# ibmpc.net
KiCad netlist of a schematic drawn in EAGLE
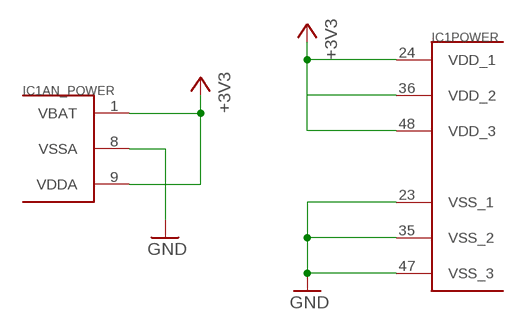
[diagram p0: schematic, sheet 1, part 1 of 2]
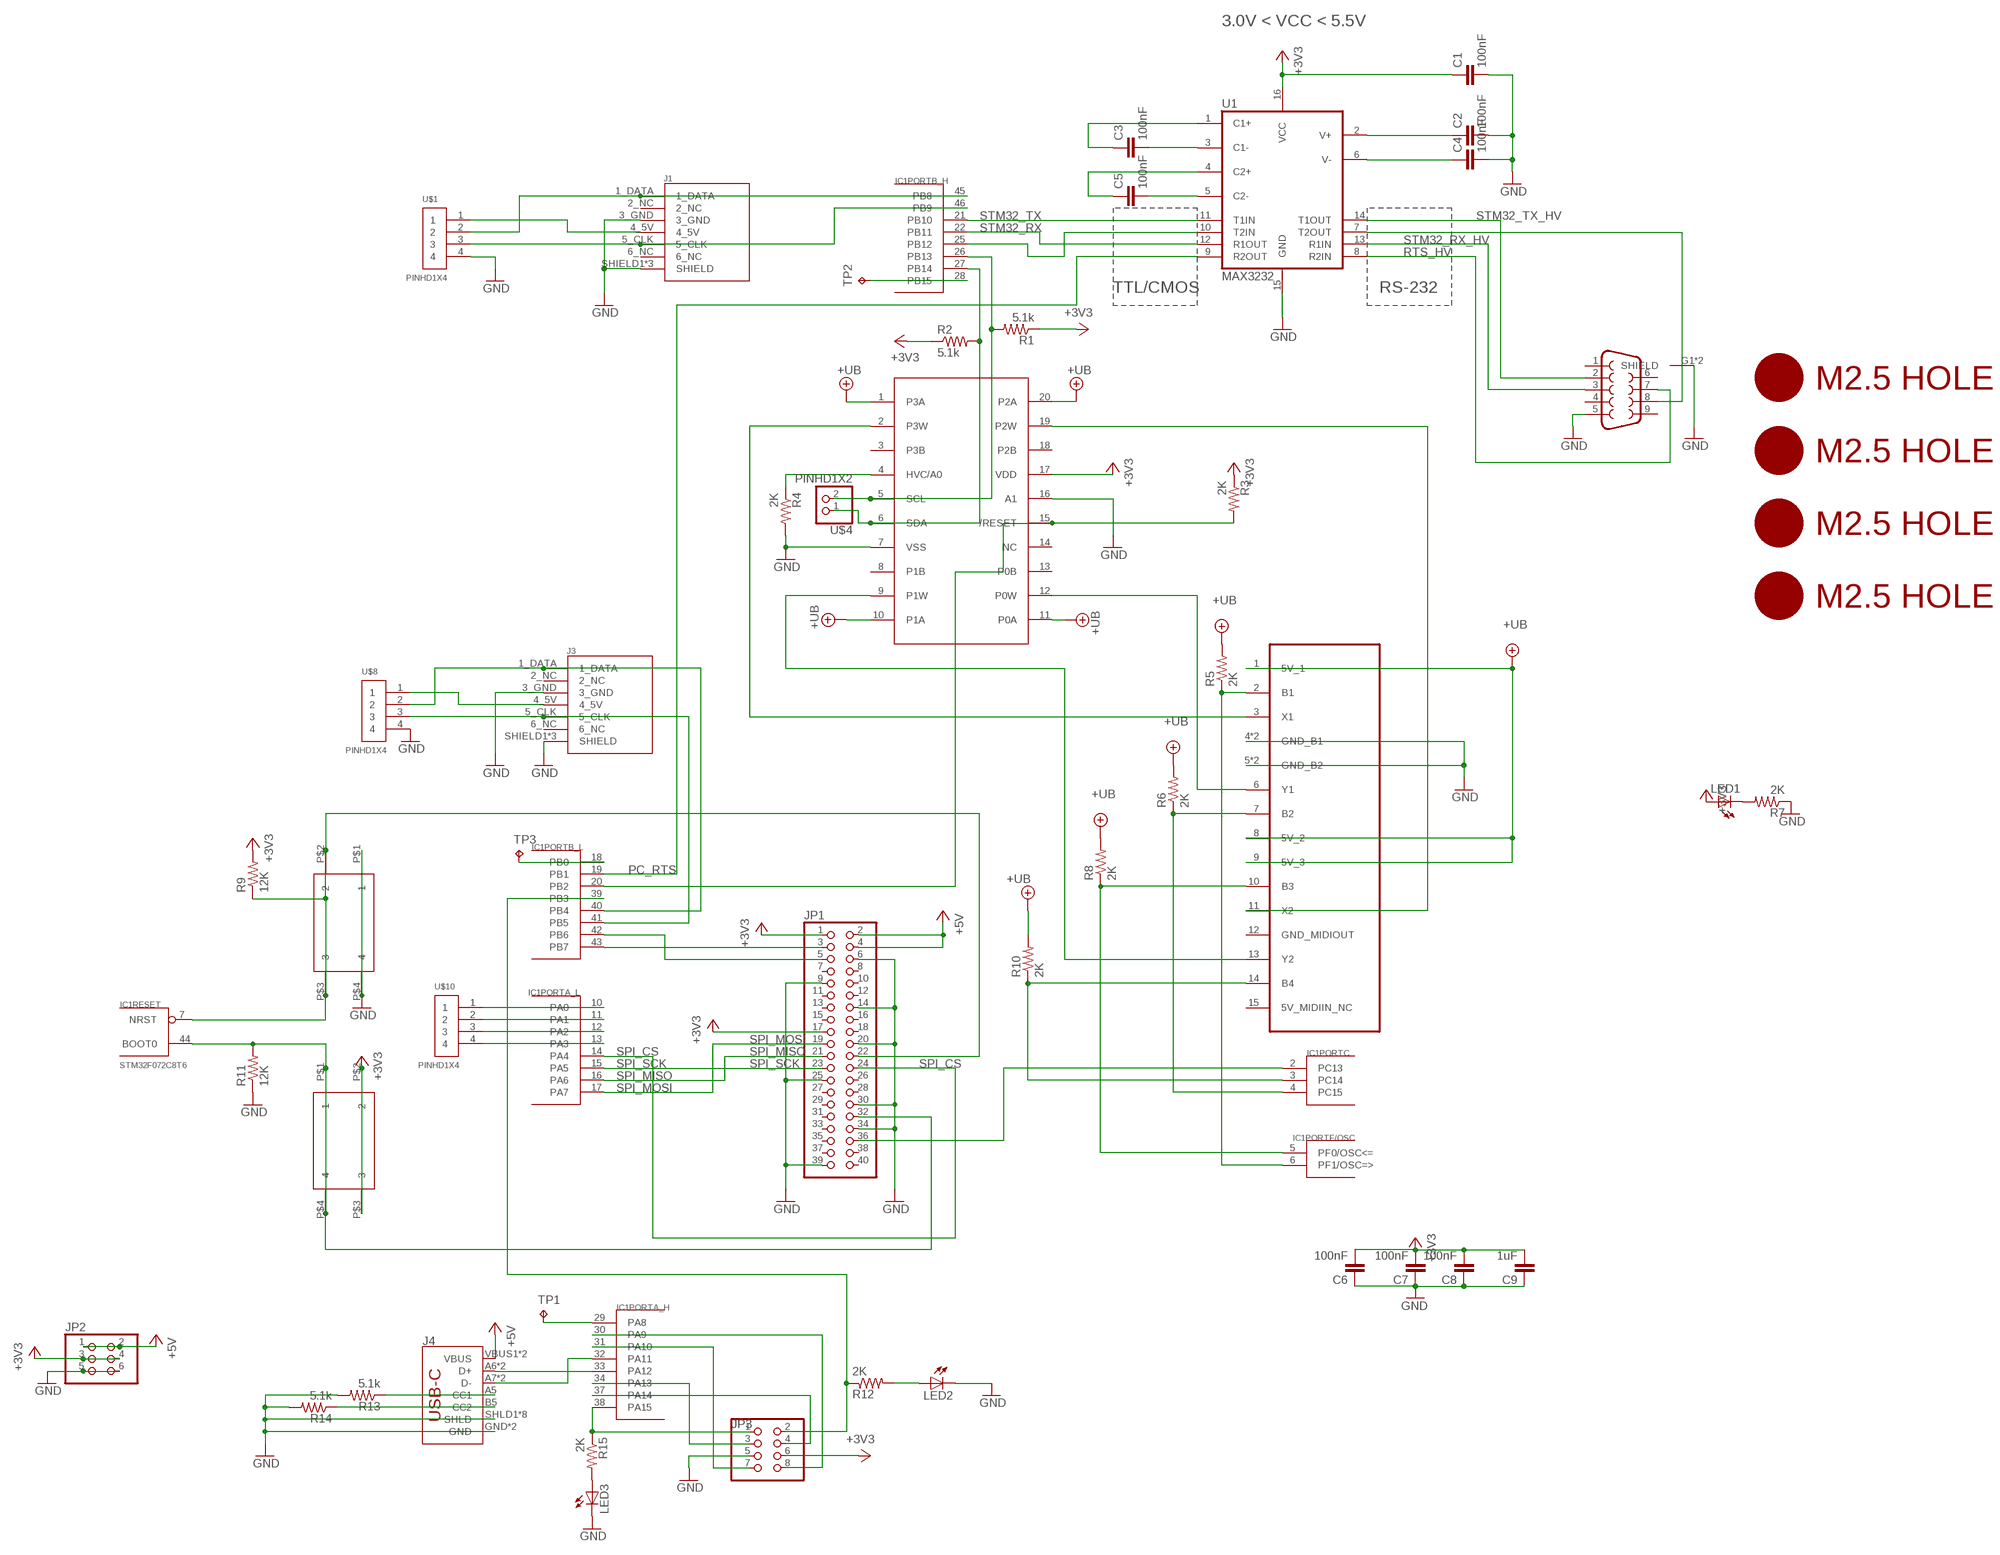
[diagram p1: schematic, sheet 1, part 2 of 2]

(export (version "E")
  (design (tool "Eeschema 10.0.6"))
  (components
    (comp (ref "C1")
      (value "100nF")
      (footprint "eagle-import:0805@1")
      (libsource (lib "eagle-import") (part "CAP0805"))
    )
    (comp (ref "C2")
      (value "100nF")
      (footprint "eagle-import:0805@1")
      (libsource (lib "eagle-import") (part "CAP0805"))
    )
    (comp (ref "C3")
      (value "100nF")
      (footprint "eagle-import:0805@1")
      (libsource (lib "eagle-import") (part "CAP0805"))
    )
    (comp (ref "C4")
      (value "100nF")
      (footprint "eagle-import:0805@1")
      (libsource (lib "eagle-import") (part "CAP0805"))
    )
    (comp (ref "C5")
      (value "100nF")
      (footprint "eagle-import:0805@1")
      (libsource (lib "eagle-import") (part "CAP0805"))
    )
    (comp (ref "C6")
      (value "100nF")
      (footprint "eagle-import:0805@1")
      (libsource (lib "eagle-import") (part "CAP0805"))
    )
    (comp (ref "C7")
      (value "100nF")
      (footprint "eagle-import:0805@1")
      (libsource (lib "eagle-import") (part "CAP0805"))
    )
    (comp (ref "C8")
      (value "100nF")
      (footprint "eagle-import:0805@1")
      (libsource (lib "eagle-import") (part "CAP0805"))
    )
    (comp (ref "C9")
      (value "1uF")
      (footprint "eagle-import:0805@1")
      (libsource (lib "eagle-import") (part "CAP0805"))
    )
    (comp (ref "IC1")
      (value "STM32F072C8T6")
      (footprint "eagle-import:TQFP48")
      (libsource (lib "eagle-import") (part "STM32F072C8T6"))
    )
    (comp (ref "J1")
      (value "DIN7")
      (footprint "eagle-import:DIN7")
      (libsource (lib "eagle-import") (part "DIN7"))
    )
    (comp (ref "J2")
      (value "DB9MALE")
      (footprint "eagle-import:DB9_MALE")
      (libsource (lib "eagle-import") (part "DB9MALE"))
    )
    (comp (ref "J3")
      (value "DIN7")
      (footprint "eagle-import:DIN7")
      (libsource (lib "eagle-import") (part "DIN7"))
    )
    (comp (ref "J4")
      (value "USB_C16PIN")
      (footprint "eagle-import:USB-C-16P")
      (libsource (lib "eagle-import") (part "USB_C16PIN"))
    )
    (comp (ref "JP1")
      (value "PINHD-2X20-BIG")
      (footprint "eagle-import:2X20-BIG")
      (libsource (lib "eagle-import") (part "PINHD-2X20-BIG"))
    )
    (comp (ref "JP2")
      (value "PINHD-2X3")
      (footprint "eagle-import:2X03")
      (libsource (lib "eagle-import") (part "PINHD-2X3"))
    )
    (comp (ref "JP3")
      (value "PINHD-2X4")
      (footprint "eagle-import:2X04")
      (libsource (lib "eagle-import") (part "PINHD-2X4"))
    )
    (comp (ref "LED1")
      (value "LEDCHIP-LED0805")
      (footprint "eagle-import:CHIP-LED0805")
      (libsource (lib "eagle-import") (part "LEDCHIP-LED0805"))
    )
    (comp (ref "LED2")
      (value "LEDCHIP-LED0805")
      (footprint "eagle-import:CHIP-LED0805")
      (libsource (lib "eagle-import") (part "LEDCHIP-LED0805"))
    )
    (comp (ref "LED3")
      (value "LEDCHIP-LED0805")
      (footprint "eagle-import:CHIP-LED0805")
      (libsource (lib "eagle-import") (part "LEDCHIP-LED0805"))
    )
    (comp (ref "R1")
      (value "5.1k")
      (footprint "eagle-import:0805")
      (libsource (lib "eagle-import") (part "RESISTOR0805-RES"))
    )
    (comp (ref "R2")
      (value "5.1k")
      (footprint "eagle-import:0805")
      (libsource (lib "eagle-import") (part "RESISTOR0805-RES"))
    )
    (comp (ref "R3")
      (value "2K")
      (footprint "eagle-import:0805")
      (libsource (lib "eagle-import") (part "RESISTOR0805-RES"))
    )
    (comp (ref "R4")
      (value "2K")
      (footprint "eagle-import:0805")
      (libsource (lib "eagle-import") (part "RESISTOR0805-RES"))
    )
    (comp (ref "R5")
      (value "2K")
      (footprint "eagle-import:0805")
      (libsource (lib "eagle-import") (part "RESISTOR0805-RES"))
    )
    (comp (ref "R6")
      (value "2K")
      (footprint "eagle-import:0805")
      (libsource (lib "eagle-import") (part "RESISTOR0805-RES"))
    )
    (comp (ref "R7")
      (value "2K")
      (footprint "eagle-import:0805")
      (libsource (lib "eagle-import") (part "RESISTOR0805-RES"))
    )
    (comp (ref "R8")
      (value "2K")
      (footprint "eagle-import:0805")
      (libsource (lib "eagle-import") (part "RESISTOR0805-RES"))
    )
    (comp (ref "R9")
      (value "12K")
      (footprint "eagle-import:0805")
      (libsource (lib "eagle-import") (part "RESISTOR0805-RES"))
    )
    (comp (ref "R10")
      (value "2K")
      (footprint "eagle-import:0805")
      (libsource (lib "eagle-import") (part "RESISTOR0805-RES"))
    )
    (comp (ref "R11")
      (value "12K")
      (footprint "eagle-import:0805")
      (libsource (lib "eagle-import") (part "RESISTOR0805-RES"))
    )
    (comp (ref "R12")
      (value "2K")
      (footprint "eagle-import:0805")
      (libsource (lib "eagle-import") (part "RESISTOR0805-RES"))
    )
    (comp (ref "R13")
      (value "5.1k")
      (footprint "eagle-import:0805")
      (libsource (lib "eagle-import") (part "RESISTOR0805-RES"))
    )
    (comp (ref "R14")
      (value "5.1k")
      (footprint "eagle-import:0805")
      (libsource (lib "eagle-import") (part "RESISTOR0805-RES"))
    )
    (comp (ref "R15")
      (value "2K")
      (footprint "eagle-import:0805")
      (libsource (lib "eagle-import") (part "RESISTOR0805-RES"))
    )
    (comp (ref "SW1")
      (value "324_SW")
      (footprint "eagle-import:342_SWICH_FOOT")
      (libsource (lib "eagle-import") (part "324_SW"))
    )
    (comp (ref "SW2")
      (value "324_SW")
      (footprint "eagle-import:342_SWICH_FOOT")
      (libsource (lib "eagle-import") (part "324_SW"))
    )
    (comp (ref "TP1")
      (value "TPTP12R")
      (footprint "eagle-import:TP12R")
      (libsource (lib "eagle-import") (part "TPTP12R"))
    )
    (comp (ref "TP2")
      (value "TPTP12R")
      (footprint "eagle-import:TP12R")
      (libsource (lib "eagle-import") (part "TPTP12R"))
    )
    (comp (ref "TP3")
      (value "TPTP12R")
      (footprint "eagle-import:TP12R")
      (libsource (lib "eagle-import") (part "TPTP12R"))
    )
    (comp (ref "U$1")
      (value "PINHD1X4")
      (footprint "eagle-import:1X04-CLEANBIG")
      (libsource (lib "eagle-import") (part "PINHD1X4"))
    )
    (comp (ref "U$2")
      (value "M2.5HOLE")
      (footprint "eagle-import:M2.5HOLE")
      (libsource (lib "eagle-import") (part "M2.5HOLE"))
    )
    (comp (ref "U$3")
      (value "M2.5HOLE")
      (footprint "eagle-import:M2.5HOLE")
      (libsource (lib "eagle-import") (part "M2.5HOLE"))
    )
    (comp (ref "U$4")
      (value "PINHD1X2")
      (footprint "eagle-import:1X02")
      (libsource (lib "eagle-import") (part "PINHD1X2"))
    )
    (comp (ref "U$5")
      (value "MCP4451")
      (footprint "eagle-import:TSSOP20")
      (libsource (lib "eagle-import") (part "MCP4451"))
    )
    (comp (ref "U$6")
      (value "M2.5HOLE")
      (footprint "eagle-import:M2.5HOLE")
      (libsource (lib "eagle-import") (part "M2.5HOLE"))
    )
    (comp (ref "U$7")
      (value "M2.5HOLE")
      (footprint "eagle-import:M2.5HOLE")
      (libsource (lib "eagle-import") (part "M2.5HOLE"))
    )
    (comp (ref "U$8")
      (value "PINHD1X4")
      (footprint "eagle-import:1X04-CLEANBIG")
      (libsource (lib "eagle-import") (part "PINHD1X4"))
    )
    (comp (ref "U$9")
      (value "GAMEPORT_15P")
      (footprint "eagle-import:DA15")
      (libsource (lib "eagle-import") (part "GAMEPORT_15P"))
    )
    (comp (ref "U$10")
      (value "PINHD1X4")
      (footprint "eagle-import:1X04-CLEANBIG")
      (libsource (lib "eagle-import") (part "PINHD1X4"))
    )
    (comp (ref "U1")
      (value "MAX3232")
      (footprint "eagle-import:SO016")
      (libsource (lib "eagle-import") (part "MAX232SOIC16"))
    )
  )
  (nets
    (net (code "1") (name "+3V3") (class "Default")
      (node (ref "C1") (pin "1") (pinfunction "1_1") (pintype "passive"))
      (node (ref "C6") (pin "2") (pinfunction "2_2") (pintype "passive"))
      (node (ref "C7") (pin "2") (pinfunction "2_2") (pintype "passive"))
      (node (ref "C8") (pin "2") (pinfunction "2_2") (pintype "passive"))
      (node (ref "C9") (pin "2") (pinfunction "2_2") (pintype "passive"))
      (node (ref "IC1") (pin "1") (pinfunction "VBAT_1") (pintype "power_in"))
      (node (ref "IC1") (pin "24") (pinfunction "VDD_1_24") (pintype "power_in"))
      (node (ref "IC1") (pin "36") (pinfunction "VDD_2_36") (pintype "power_in"))
      (node (ref "IC1") (pin "48") (pinfunction "VDD_3_48") (pintype "power_in"))
      (node (ref "IC1") (pin "9") (pinfunction "VDDA_9") (pintype "power_in"))
      (node (ref "JP1") (pin "1") (pinfunction "1_1") (pintype "passive"))
      (node (ref "JP1") (pin "17") (pinfunction "17_17") (pintype "passive"))
      (node (ref "JP2") (pin "3") (pinfunction "3_3") (pintype "passive"))
      (node (ref "JP2") (pin "4") (pinfunction "4_4") (pintype "passive"))
      (node (ref "JP3") (pin "6") (pinfunction "6_6") (pintype "passive"))
      (node (ref "LED1") (pin "A") (pinfunction "A_A") (pintype "passive"))
      (node (ref "R1") (pin "1") (pinfunction "1_1") (pintype "passive"))
      (node (ref "R2") (pin "1") (pinfunction "1_1") (pintype "passive"))
      (node (ref "R3") (pin "1") (pinfunction "1_1") (pintype "passive"))
      (node (ref "R9") (pin "2") (pinfunction "2_2") (pintype "passive"))
      (node (ref "SW2") (pin "P$2") (pinfunction "2_P$2") (pintype "bidirectional"))
      (node (ref "SW2") (pin "P$3") (pinfunction "3_P$3") (pintype "bidirectional"))
      (node (ref "U$5") (pin "17") (pinfunction "VDD_17") (pintype "bidirectional"))
      (node (ref "U1") (pin "16") (pinfunction "VCC_16") (pintype "bidirectional"))
    )
    (net (code "2") (name "+5V") (class "Default")
      (node (ref "J4") (pin "VBUS1") (pinfunction "VBUS_VBUS1") (pintype "bidirectional"))
      (node (ref "J4") (pin "VBUS2") (pinfunction "VBUS_VBUS2") (pintype "bidirectional"))
      (node (ref "JP1") (pin "2") (pinfunction "2_2") (pintype "passive"))
      (node (ref "JP1") (pin "4") (pinfunction "4_4") (pintype "passive"))
      (node (ref "JP2") (pin "1") (pinfunction "1_1") (pintype "passive"))
      (node (ref "JP2") (pin "2") (pinfunction "2_2") (pintype "passive"))
    )
    (net (code "3") (name "+UB") (class "Default")
      (node (ref "R10") (pin "2") (pinfunction "2_2") (pintype "passive"))
      (node (ref "R5") (pin "2") (pinfunction "2_2") (pintype "passive"))
      (node (ref "R6") (pin "2") (pinfunction "2_2") (pintype "passive"))
      (node (ref "R8") (pin "2") (pinfunction "2_2") (pintype "passive"))
      (node (ref "U$5") (pin "1") (pinfunction "P3A_1") (pintype "bidirectional"))
      (node (ref "U$5") (pin "10") (pinfunction "P1A_10") (pintype "bidirectional"))
      (node (ref "U$5") (pin "11") (pinfunction "P0A_11") (pintype "bidirectional"))
      (node (ref "U$5") (pin "20") (pinfunction "P2A_20") (pintype "bidirectional"))
      (node (ref "U$9") (pin "1") (pinfunction "5V_1_1") (pintype "bidirectional"))
      (node (ref "U$9") (pin "8") (pinfunction "5V_2_8") (pintype "bidirectional"))
      (node (ref "U$9") (pin "9") (pinfunction "5V_3_9") (pintype "bidirectional"))
    )
    (net (code "4") (name "/PC_RTS") (class "Default")
      (node (ref "IC1") (pin "19") (pinfunction "PB1_19") (pintype "bidirectional"))
      (node (ref "U1") (pin "9") (pinfunction "R2OUT_9") (pintype "output"))
    )
    (net (code "5") (name "/RTS_HV") (class "Default")
      (node (ref "J2") (pin "7") (pinfunction "7_7") (pintype "passive"))
      (node (ref "U1") (pin "8") (pinfunction "R2IN_8") (pintype "input"))
    )
    (net (code "6") (name "/SPI_CS") (class "Default")
      (node (ref "IC1") (pin "14") (pinfunction "PA4_14") (pintype "bidirectional"))
      (node (ref "JP1") (pin "24") (pinfunction "24_24") (pintype "passive"))
    )
    (net (code "7") (name "/SPI_MISO") (class "Default")
      (node (ref "IC1") (pin "16") (pinfunction "PA6_16") (pintype "bidirectional"))
      (node (ref "JP1") (pin "21") (pinfunction "21_21") (pintype "passive"))
    )
    (net (code "8") (name "/SPI_MOSI") (class "Default")
      (node (ref "IC1") (pin "17") (pinfunction "PA7_17") (pintype "bidirectional"))
      (node (ref "JP1") (pin "19") (pinfunction "19_19") (pintype "passive"))
    )
    (net (code "9") (name "/SPI_SCK") (class "Default")
      (node (ref "IC1") (pin "15") (pinfunction "PA5_15") (pintype "bidirectional"))
      (node (ref "JP1") (pin "23") (pinfunction "23_23") (pintype "passive"))
    )
    (net (code "10") (name "/STM32_RX") (class "Default")
      (node (ref "IC1") (pin "22") (pinfunction "PB11_22") (pintype "bidirectional"))
      (node (ref "U1") (pin "12") (pinfunction "R1OUT_12") (pintype "output"))
    )
    (net (code "11") (name "/STM32_RX_HV") (class "Default")
      (node (ref "J2") (pin "3") (pinfunction "3_3") (pintype "passive"))
      (node (ref "U1") (pin "13") (pinfunction "R1IN_13") (pintype "input"))
    )
    (net (code "12") (name "/STM32_TX") (class "Default")
      (node (ref "IC1") (pin "21") (pinfunction "PB10_21") (pintype "bidirectional"))
      (node (ref "U1") (pin "11") (pinfunction "T1IN_11") (pintype "input"))
    )
    (net (code "13") (name "/STM32_TX_HV") (class "Default")
      (node (ref "J2") (pin "2") (pinfunction "2_2") (pintype "passive"))
      (node (ref "U1") (pin "14") (pinfunction "T1OUT_14") (pintype "output"))
    )
    (net (code "14") (name "GND") (class "Default")
      (node (ref "C1") (pin "2") (pinfunction "2_2") (pintype "passive"))
      (node (ref "C2") (pin "2") (pinfunction "2_2") (pintype "passive"))
      (node (ref "C4") (pin "2") (pinfunction "2_2") (pintype "passive"))
      (node (ref "C6") (pin "1") (pinfunction "1_1") (pintype "passive"))
      (node (ref "C7") (pin "1") (pinfunction "1_1") (pintype "passive"))
      (node (ref "C8") (pin "1") (pinfunction "1_1") (pintype "passive"))
      (node (ref "C9") (pin "1") (pinfunction "1_1") (pintype "passive"))
      (node (ref "IC1") (pin "23") (pinfunction "VSS_1_23") (pintype "power_in"))
      (node (ref "IC1") (pin "35") (pinfunction "VSS_2_35") (pintype "power_in"))
      (node (ref "IC1") (pin "47") (pinfunction "VSS_3_47") (pintype "power_in"))
      (node (ref "IC1") (pin "8") (pinfunction "VSSA_8") (pintype "power_in"))
      (node (ref "J1") (pin "3_GND") (pinfunction "3_GND_3_GND") (pintype "bidirectional"))
      (node (ref "J1") (pin "SHIELD1") (pinfunction "SHIELD_SHIELD1") (pintype "bidirectional"))
      (node (ref "J1") (pin "SHIELD2") (pinfunction "SHIELD_SHIELD2") (pintype "bidirectional"))
      (node (ref "J1") (pin "SHIELD3") (pinfunction "SHIELD_SHIELD3") (pintype "bidirectional"))
      (node (ref "J2") (pin "5") (pinfunction "5_5") (pintype "passive"))
      (node (ref "J2") (pin "G1") (pinfunction "SHIELD_G1") (pintype "bidirectional"))
      (node (ref "J2") (pin "G2") (pinfunction "SHIELD_G2") (pintype "bidirectional"))
      (node (ref "J3") (pin "3_GND") (pinfunction "3_GND_3_GND") (pintype "bidirectional"))
      (node (ref "J3") (pin "SHIELD1") (pinfunction "SHIELD_SHIELD1") (pintype "bidirectional"))
      (node (ref "J3") (pin "SHIELD2") (pinfunction "SHIELD_SHIELD2") (pintype "bidirectional"))
      (node (ref "J3") (pin "SHIELD3") (pinfunction "SHIELD_SHIELD3") (pintype "bidirectional"))
      (node (ref "J4") (pin "GND") (pinfunction "GND_GND") (pintype "bidirectional"))
      (node (ref "J4") (pin "GND2") (pinfunction "GND_GND2") (pintype "bidirectional"))
      (node (ref "J4") (pin "SHLD1") (pinfunction "SHLD_SHLD1") (pintype "bidirectional"))
      (node (ref "J4") (pin "SHLD2") (pinfunction "SHLD_SHLD2") (pintype "bidirectional"))
      (node (ref "J4") (pin "SHLD3") (pinfunction "SHLD_SHLD3") (pintype "bidirectional"))
      (node (ref "J4") (pin "SHLD4") (pinfunction "SHLD_SHLD4") (pintype "bidirectional"))
      (node (ref "J4") (pin "SHLD5") (pinfunction "SHLD_SHLD5") (pintype "bidirectional"))
      (node (ref "J4") (pin "SHLD6") (pinfunction "SHLD_SHLD6") (pintype "bidirectional"))
      (node (ref "J4") (pin "SHLD7") (pinfunction "SHLD_SHLD7") (pintype "bidirectional"))
      (node (ref "J4") (pin "SHLD8") (pinfunction "SHLD_SHLD8") (pintype "bidirectional"))
      (node (ref "JP1") (pin "14") (pinfunction "14_14") (pintype "passive"))
      (node (ref "JP1") (pin "20") (pinfunction "20_20") (pintype "passive"))
      (node (ref "JP1") (pin "25") (pinfunction "25_25") (pintype "passive"))
      (node (ref "JP1") (pin "30") (pinfunction "30_30") (pintype "passive"))
      (node (ref "JP1") (pin "34") (pinfunction "34_34") (pintype "passive"))
      (node (ref "JP1") (pin "39") (pinfunction "39_39") (pintype "passive"))
      (node (ref "JP1") (pin "6") (pinfunction "6_6") (pintype "passive"))
      (node (ref "JP1") (pin "9") (pinfunction "9_9") (pintype "passive"))
      (node (ref "JP2") (pin "5") (pinfunction "5_5") (pintype "passive"))
      (node (ref "JP2") (pin "6") (pinfunction "6_6") (pintype "passive"))
      (node (ref "JP3") (pin "5") (pinfunction "5_5") (pintype "passive"))
      (node (ref "LED2") (pin "C") (pinfunction "C_C") (pintype "passive"))
      (node (ref "LED3") (pin "C") (pinfunction "C_C") (pintype "passive"))
      (node (ref "R11") (pin "1") (pinfunction "1_1") (pintype "passive"))
      (node (ref "R13") (pin "2") (pinfunction "2_2") (pintype "passive"))
      (node (ref "R14") (pin "2") (pinfunction "2_2") (pintype "passive"))
      (node (ref "R4") (pin "2") (pinfunction "2_2") (pintype "passive"))
      (node (ref "R7") (pin "1") (pinfunction "1_1") (pintype "passive"))
      (node (ref "SW1") (pin "P$1") (pinfunction "1_P$1") (pintype "bidirectional"))
      (node (ref "SW1") (pin "P$4") (pinfunction "4_P$4") (pintype "bidirectional"))
      (node (ref "U$1") (pin "4") (pinfunction "4_4") (pintype "bidirectional"))
      (node (ref "U$5") (pin "16") (pinfunction "A1_16") (pintype "bidirectional"))
      (node (ref "U$5") (pin "7") (pinfunction "VSS_7") (pintype "bidirectional"))
      (node (ref "U$8") (pin "4") (pinfunction "4_4") (pintype "bidirectional"))
      (node (ref "U$9") (pin "4") (pinfunction "GND_B1_4") (pintype "bidirectional"))
      (node (ref "U$9") (pin "5") (pinfunction "GND_B2_5") (pintype "bidirectional"))
      (node (ref "U$9") (pin "G1") (pinfunction "GND_B1_G1") (pintype "bidirectional"))
      (node (ref "U$9") (pin "G2") (pinfunction "GND_B2_G2") (pintype "bidirectional"))
      (node (ref "U1") (pin "15") (pinfunction "GND_15") (pintype "bidirectional"))
    )
    (net (code "15") (name "Net-(IC1B-PA8)") (class "Default")
      (node (ref "IC1") (pin "29") (pinfunction "PA8_29") (pintype "bidirectional"))
      (node (ref "TP1") (pin "TP") (pinfunction "TP_TP") (pintype "input"))
    )
    (net (code "16") (name "Net-(IC1B-PA9)") (class "Default")
      (node (ref "IC1") (pin "30") (pinfunction "PA9_30") (pintype "bidirectional"))
      (node (ref "JP3") (pin "8") (pinfunction "8_8") (pintype "passive"))
    )
    (net (code "17") (name "Net-(IC1B-PA10)") (class "Default")
      (node (ref "IC1") (pin "31") (pinfunction "PA10_31") (pintype "bidirectional"))
      (node (ref "JP3") (pin "7") (pinfunction "7_7") (pintype "passive"))
    )
    (net (code "18") (name "Net-(IC1B-PA11)") (class "Default")
      (node (ref "IC1") (pin "32") (pinfunction "PA11_32") (pintype "bidirectional"))
      (node (ref "J4") (pin "A7") (pinfunction "D-_A7") (pintype "bidirectional"))
      (node (ref "J4") (pin "B7") (pinfunction "D-_B7") (pintype "bidirectional"))
    )
    (net (code "19") (name "Net-(IC1B-PA12)") (class "Default")
      (node (ref "IC1") (pin "33") (pinfunction "PA12_33") (pintype "bidirectional"))
      (node (ref "J4") (pin "A6") (pinfunction "D+_A6") (pintype "bidirectional"))
      (node (ref "J4") (pin "B6") (pinfunction "D+_B6") (pintype "bidirectional"))
    )
    (net (code "20") (name "Net-(IC1B-PA13)") (class "Default")
      (node (ref "IC1") (pin "34") (pinfunction "PA13_34") (pintype "bidirectional"))
      (node (ref "JP3") (pin "3") (pinfunction "3_3") (pintype "passive"))
    )
    (net (code "21") (name "Net-(IC1B-PA14)") (class "Default")
      (node (ref "IC1") (pin "37") (pinfunction "PA14_37") (pintype "bidirectional"))
      (node (ref "JP3") (pin "4") (pinfunction "4_4") (pintype "passive"))
    )
    (net (code "22") (name "Net-(IC1B-PA15)") (class "Default")
      (node (ref "IC1") (pin "38") (pinfunction "PA15_38") (pintype "bidirectional"))
      (node (ref "JP3") (pin "1") (pinfunction "1_1") (pintype "passive"))
      (node (ref "R15") (pin "1") (pinfunction "1_1") (pintype "passive"))
    )
    (net (code "23") (name "Net-(IC1C-PA0)") (class "Default")
      (node (ref "IC1") (pin "10") (pinfunction "PA0_10") (pintype "bidirectional"))
      (node (ref "U$10") (pin "1") (pinfunction "1_1") (pintype "bidirectional"))
    )
    (net (code "24") (name "Net-(IC1C-PA1)") (class "Default")
      (node (ref "IC1") (pin "11") (pinfunction "PA1_11") (pintype "bidirectional"))
      (node (ref "U$10") (pin "2") (pinfunction "2_2") (pintype "bidirectional"))
    )
    (net (code "25") (name "Net-(IC1C-PA2)") (class "Default")
      (node (ref "IC1") (pin "12") (pinfunction "PA2_12") (pintype "bidirectional"))
      (node (ref "U$10") (pin "3") (pinfunction "3_3") (pintype "bidirectional"))
    )
    (net (code "26") (name "Net-(IC1C-PA3)") (class "Default")
      (node (ref "IC1") (pin "13") (pinfunction "PA3_13") (pintype "bidirectional"))
      (node (ref "U$10") (pin "4") (pinfunction "4_4") (pintype "bidirectional"))
    )
    (net (code "27") (name "Net-(IC1D-PB8)") (class "Default")
      (node (ref "IC1") (pin "45") (pinfunction "PB8_45") (pintype "bidirectional"))
      (node (ref "J1") (pin "1_DATA") (pinfunction "1_DATA_1_DATA") (pintype "bidirectional"))
      (node (ref "U$1") (pin "2") (pinfunction "2_2") (pintype "bidirectional"))
    )
    (net (code "28") (name "Net-(IC1D-PB9)") (class "Default")
      (node (ref "IC1") (pin "46") (pinfunction "PB9_46") (pintype "bidirectional"))
      (node (ref "J1") (pin "5_CLK") (pinfunction "5_CLK_5_CLK") (pintype "bidirectional"))
      (node (ref "U$1") (pin "3") (pinfunction "3_3") (pintype "bidirectional"))
    )
    (net (code "29") (name "Net-(IC1D-PB12)") (class "Default")
      (node (ref "IC1") (pin "25") (pinfunction "PB12_25") (pintype "bidirectional"))
      (node (ref "U1") (pin "10") (pinfunction "T2IN_10") (pintype "input"))
    )
    (net (code "30") (name "Net-(IC1D-PB13)") (class "Default")
      (node (ref "IC1") (pin "26") (pinfunction "PB13_26") (pintype "bidirectional"))
      (node (ref "R1") (pin "2") (pinfunction "2_2") (pintype "passive"))
      (node (ref "U$4") (pin "2") (pinfunction "2_2") (pintype "passive"))
      (node (ref "U$5") (pin "5") (pinfunction "SCL_5") (pintype "bidirectional"))
    )
    (net (code "31") (name "Net-(IC1D-PB14)") (class "Default")
      (node (ref "IC1") (pin "27") (pinfunction "PB14_27") (pintype "bidirectional"))
      (node (ref "R2") (pin "2") (pinfunction "2_2") (pintype "passive"))
      (node (ref "U$4") (pin "1") (pinfunction "1_1") (pintype "passive"))
      (node (ref "U$5") (pin "6") (pinfunction "SDA_6") (pintype "bidirectional"))
    )
    (net (code "32") (name "Net-(IC1D-PB15)") (class "Default")
      (node (ref "IC1") (pin "28") (pinfunction "PB15_28") (pintype "bidirectional"))
      (node (ref "TP2") (pin "TP") (pinfunction "TP_TP") (pintype "input"))
    )
    (net (code "33") (name "Net-(IC1E-PB0)") (class "Default")
      (node (ref "IC1") (pin "18") (pinfunction "PB0_18") (pintype "bidirectional"))
      (node (ref "TP3") (pin "TP") (pinfunction "TP_TP") (pintype "input"))
    )
    (net (code "34") (name "Net-(IC1E-PB2)") (class "Default")
      (node (ref "IC1") (pin "20") (pinfunction "PB2_20") (pintype "bidirectional"))
      (node (ref "R3") (pin "2") (pinfunction "2_2") (pintype "passive"))
      (node (ref "U$5") (pin "15") (pinfunction "/RESET_15") (pintype "bidirectional"))
    )
    (net (code "35") (name "Net-(IC1E-PB3)") (class "Default")
      (node (ref "IC1") (pin "39") (pinfunction "PB3_39") (pintype "bidirectional"))
      (node (ref "JP3") (pin "2") (pinfunction "2_2") (pintype "passive"))
      (node (ref "R12") (pin "1") (pinfunction "1_1") (pintype "passive"))
    )
    (net (code "36") (name "Net-(IC1E-PB4)") (class "Default")
      (node (ref "IC1") (pin "40") (pinfunction "PB4_40") (pintype "bidirectional"))
      (node (ref "J3") (pin "1_DATA") (pinfunction "1_DATA_1_DATA") (pintype "bidirectional"))
      (node (ref "U$8") (pin "2") (pinfunction "2_2") (pintype "bidirectional"))
    )
    (net (code "37") (name "Net-(IC1E-PB5)") (class "Default")
      (node (ref "IC1") (pin "41") (pinfunction "PB5_41") (pintype "bidirectional"))
      (node (ref "J3") (pin "5_CLK") (pinfunction "5_CLK_5_CLK") (pintype "bidirectional"))
      (node (ref "U$8") (pin "3") (pinfunction "3_3") (pintype "bidirectional"))
    )
    (net (code "38") (name "Net-(IC1E-PB6)") (class "Default")
      (node (ref "IC1") (pin "42") (pinfunction "PB6_42") (pintype "bidirectional"))
      (node (ref "JP1") (pin "5") (pinfunction "5_5") (pintype "passive"))
    )
    (net (code "39") (name "Net-(IC1E-PB7)") (class "Default")
      (node (ref "IC1") (pin "43") (pinfunction "PB7_43") (pintype "bidirectional"))
      (node (ref "JP1") (pin "3") (pinfunction "3_3") (pintype "passive"))
    )
    (net (code "40") (name "Net-(IC1F-PC13)") (class "Default")
      (node (ref "IC1") (pin "2") (pinfunction "PC13_2") (pintype "bidirectional"))
      (node (ref "JP1") (pin "36") (pinfunction "36_36") (pintype "passive"))
    )
    (net (code "41") (name "Net-(IC1F-PC14)") (class "Default")
      (node (ref "IC1") (pin "3") (pinfunction "PC14_3") (pintype "bidirectional"))
      (node (ref "R10") (pin "1") (pinfunction "1_1") (pintype "passive"))
      (node (ref "U$9") (pin "14") (pinfunction "B4_14") (pintype "bidirectional"))
    )
    (net (code "42") (name "Net-(IC1F-PC15)") (class "Default")
      (node (ref "IC1") (pin "4") (pinfunction "PC15_4") (pintype "bidirectional"))
      (node (ref "R6") (pin "1") (pinfunction "1_1") (pintype "passive"))
      (node (ref "U$9") (pin "7") (pinfunction "B2_7") (pintype "bidirectional"))
    )
    (net (code "43") (name "Net-(IC1G-PF0{slash}OSC<=)") (class "Default")
      (node (ref "IC1") (pin "5") (pinfunction "PF0/OSC<=_5") (pintype "bidirectional"))
      (node (ref "R8") (pin "1") (pinfunction "1_1") (pintype "passive"))
      (node (ref "U$9") (pin "10") (pinfunction "B3_10") (pintype "bidirectional"))
    )
    (net (code "44") (name "Net-(IC1G-PF1{slash}OSC=>)") (class "Default")
      (node (ref "IC1") (pin "6") (pinfunction "PF1/OSC=>_6") (pintype "bidirectional"))
      (node (ref "R5") (pin "1") (pinfunction "1_1") (pintype "passive"))
      (node (ref "U$9") (pin "2") (pinfunction "B1_2") (pintype "bidirectional"))
    )
    (net (code "45") (name "Net-(IC1I-BOOT0)") (class "Default")
      (node (ref "IC1") (pin "44") (pinfunction "BOOT0_44") (pintype "input"))
      (node (ref "JP1") (pin "32") (pinfunction "32_32") (pintype "passive"))
      (node (ref "R11") (pin "2") (pinfunction "2_2") (pintype "passive"))
      (node (ref "SW2") (pin "P$1") (pinfunction "1_P$1") (pintype "bidirectional"))
      (node (ref "SW2") (pin "P$4") (pinfunction "4_P$4") (pintype "bidirectional"))
    )
    (net (code "46") (name "Net-(IC1I-NRST)") (class "Default")
      (node (ref "IC1") (pin "7") (pinfunction "NRST_7") (pintype "input"))
      (node (ref "JP1") (pin "22") (pinfunction "22_22") (pintype "passive"))
      (node (ref "R9") (pin "1") (pinfunction "1_1") (pintype "passive"))
      (node (ref "SW1") (pin "P$2") (pinfunction "2_P$2") (pintype "bidirectional"))
      (node (ref "SW1") (pin "P$3") (pinfunction "3_P$3") (pintype "bidirectional"))
    )
    (net (code "47") (name "Net-(J1-Pad4_5V)") (class "Default")
      (node (ref "J1") (pin "4_5V") (pinfunction "4_5V_4_5V") (pintype "bidirectional"))
      (node (ref "U$1") (pin "1") (pinfunction "1_1") (pintype "bidirectional"))
    )
    (net (code "48") (name "Net-(J3-Pad4_5V)") (class "Default")
      (node (ref "J3") (pin "4_5V") (pinfunction "4_5V_4_5V") (pintype "bidirectional"))
      (node (ref "U$8") (pin "1") (pinfunction "1_1") (pintype "bidirectional"))
    )
    (net (code "49") (name "Net-(J4-CC1)") (class "Default")
      (node (ref "J4") (pin "A5") (pinfunction "CC1_A5") (pintype "bidirectional"))
      (node (ref "R13") (pin "1") (pinfunction "1_1") (pintype "passive"))
    )
    (net (code "50") (name "Net-(J4-CC2)") (class "Default")
      (node (ref "J4") (pin "B5") (pinfunction "CC2_B5") (pintype "bidirectional"))
      (node (ref "R14") (pin "1") (pinfunction "1_1") (pintype "passive"))
    )
    (net (code "51") (name "Net-(LED1-PadC)") (class "Default")
      (node (ref "LED1") (pin "C") (pinfunction "C_C") (pintype "passive"))
      (node (ref "R7") (pin "2") (pinfunction "2_2") (pintype "passive"))
    )
    (net (code "52") (name "Net-(LED2-PadA)") (class "Default")
      (node (ref "LED2") (pin "A") (pinfunction "A_A") (pintype "passive"))
      (node (ref "R12") (pin "2") (pinfunction "2_2") (pintype "passive"))
    )
    (net (code "53") (name "Net-(LED3-PadA)") (class "Default")
      (node (ref "LED3") (pin "A") (pinfunction "A_A") (pintype "passive"))
      (node (ref "R15") (pin "2") (pinfunction "2_2") (pintype "passive"))
    )
    (net (code "54") (name "Net-(U$5-HVC{slash}A0)") (class "Default")
      (node (ref "R4") (pin "1") (pinfunction "1_1") (pintype "passive"))
      (node (ref "U$5") (pin "4") (pinfunction "HVC/A0_4") (pintype "bidirectional"))
    )
    (net (code "55") (name "Net-(U$5-P0W)") (class "Default")
      (node (ref "U$5") (pin "12") (pinfunction "P0W_12") (pintype "bidirectional"))
      (node (ref "U$9") (pin "6") (pinfunction "Y1_6") (pintype "bidirectional"))
    )
    (net (code "56") (name "Net-(U$5-P1W)") (class "Default")
      (node (ref "U$5") (pin "9") (pinfunction "P1W_9") (pintype "bidirectional"))
      (node (ref "U$9") (pin "13") (pinfunction "Y2_13") (pintype "bidirectional"))
    )
    (net (code "57") (name "Net-(U$5-P2W)") (class "Default")
      (node (ref "U$5") (pin "19") (pinfunction "P2W_19") (pintype "bidirectional"))
      (node (ref "U$9") (pin "11") (pinfunction "X2_11") (pintype "bidirectional"))
    )
    (net (code "58") (name "Net-(U$5-P3W)") (class "Default")
      (node (ref "U$5") (pin "2") (pinfunction "P3W_2") (pintype "bidirectional"))
      (node (ref "U$9") (pin "3") (pinfunction "X1_3") (pintype "bidirectional"))
    )
    (net (code "59") (name "Net-(U1-C1+)") (class "Default")
      (node (ref "C3") (pin "1") (pinfunction "1_1") (pintype "passive"))
      (node (ref "U1") (pin "1") (pinfunction "C1+_1") (pintype "bidirectional"))
    )
    (net (code "60") (name "Net-(U1-C1-)") (class "Default")
      (node (ref "C3") (pin "2") (pinfunction "2_2") (pintype "passive"))
      (node (ref "U1") (pin "3") (pinfunction "C1-_3") (pintype "bidirectional"))
    )
    (net (code "61") (name "Net-(U1-C2+)") (class "Default")
      (node (ref "C5") (pin "1") (pinfunction "1_1") (pintype "passive"))
      (node (ref "U1") (pin "4") (pinfunction "C2+_4") (pintype "bidirectional"))
    )
    (net (code "62") (name "Net-(U1-C2-)") (class "Default")
      (node (ref "C5") (pin "2") (pinfunction "2_2") (pintype "passive"))
      (node (ref "U1") (pin "5") (pinfunction "C2-_5") (pintype "bidirectional"))
    )
    (net (code "63") (name "Net-(U1-T2OUT)") (class "Default")
      (node (ref "J2") (pin "8") (pinfunction "8_8") (pintype "passive"))
      (node (ref "U1") (pin "7") (pinfunction "T2OUT_7") (pintype "output"))
    )
    (net (code "64") (name "Net-(U1-V+)") (class "Default")
      (node (ref "C2") (pin "1") (pinfunction "1_1") (pintype "passive"))
      (node (ref "U1") (pin "2") (pinfunction "V+_2") (pintype "bidirectional"))
    )
    (net (code "65") (name "Net-(U1-V-)") (class "Default")
      (node (ref "C4") (pin "1") (pinfunction "1_1") (pintype "passive"))
      (node (ref "U1") (pin "6") (pinfunction "V-_6") (pintype "bidirectional"))
    )
    (net (code "66") (name "unconnected-(J1-Pad2_NC)") (class "Default")
      (node (ref "J1") (pin "2_NC") (pinfunction "2_NC_2_NC") (pintype "bidirectional"))
    )
    (net (code "67") (name "unconnected-(J1-Pad6_NC)") (class "Default")
      (node (ref "J1") (pin "6_NC") (pinfunction "6_NC_6_NC") (pintype "bidirectional"))
    )
    (net (code "68") (name "unconnected-(J2-Pad1)") (class "Default")
      (node (ref "J2") (pin "1") (pinfunction "1_1") (pintype "passive"))
    )
    (net (code "69") (name "unconnected-(J2-Pad4)") (class "Default")
      (node (ref "J2") (pin "4") (pinfunction "4_4") (pintype "passive"))
    )
    (net (code "70") (name "unconnected-(J2-Pad6)") (class "Default")
      (node (ref "J2") (pin "6") (pinfunction "6_6") (pintype "passive"))
    )
    (net (code "71") (name "unconnected-(J2-Pad9)") (class "Default")
      (node (ref "J2") (pin "9") (pinfunction "9_9") (pintype "passive"))
    )
    (net (code "72") (name "unconnected-(J3-Pad2_NC)") (class "Default")
      (node (ref "J3") (pin "2_NC") (pinfunction "2_NC_2_NC") (pintype "bidirectional"))
    )
    (net (code "73") (name "unconnected-(J3-Pad6_NC)") (class "Default")
      (node (ref "J3") (pin "6_NC") (pinfunction "6_NC_6_NC") (pintype "bidirectional"))
    )
    (net (code "74") (name "unconnected-(JP1-Pad7)") (class "Default")
      (node (ref "JP1") (pin "7") (pinfunction "7_7") (pintype "passive"))
    )
    (net (code "75") (name "unconnected-(JP1-Pad8)") (class "Default")
      (node (ref "JP1") (pin "8") (pinfunction "8_8") (pintype "passive"))
    )
    (net (code "76") (name "unconnected-(JP1-Pad10)") (class "Default")
      (node (ref "JP1") (pin "10") (pinfunction "10_10") (pintype "passive"))
    )
    (net (code "77") (name "unconnected-(JP1-Pad11)") (class "Default")
      (node (ref "JP1") (pin "11") (pinfunction "11_11") (pintype "passive"))
    )
    (net (code "78") (name "unconnected-(JP1-Pad12)") (class "Default")
      (node (ref "JP1") (pin "12") (pinfunction "12_12") (pintype "passive"))
    )
    (net (code "79") (name "unconnected-(JP1-Pad13)") (class "Default")
      (node (ref "JP1") (pin "13") (pinfunction "13_13") (pintype "passive"))
    )
    (net (code "80") (name "unconnected-(JP1-Pad15)") (class "Default")
      (node (ref "JP1") (pin "15") (pinfunction "15_15") (pintype "passive"))
    )
    (net (code "81") (name "unconnected-(JP1-Pad16)") (class "Default")
      (node (ref "JP1") (pin "16") (pinfunction "16_16") (pintype "passive"))
    )
    (net (code "82") (name "unconnected-(JP1-Pad18)") (class "Default")
      (node (ref "JP1") (pin "18") (pinfunction "18_18") (pintype "passive"))
    )
    (net (code "83") (name "unconnected-(JP1-Pad26)") (class "Default")
      (node (ref "JP1") (pin "26") (pinfunction "26_26") (pintype "passive"))
    )
    (net (code "84") (name "unconnected-(JP1-Pad27)") (class "Default")
      (node (ref "JP1") (pin "27") (pinfunction "27_27") (pintype "passive"))
    )
    (net (code "85") (name "unconnected-(JP1-Pad28)") (class "Default")
      (node (ref "JP1") (pin "28") (pinfunction "28_28") (pintype "passive"))
    )
    (net (code "86") (name "unconnected-(JP1-Pad29)") (class "Default")
      (node (ref "JP1") (pin "29") (pinfunction "29_29") (pintype "passive"))
    )
    (net (code "87") (name "unconnected-(JP1-Pad31)") (class "Default")
      (node (ref "JP1") (pin "31") (pinfunction "31_31") (pintype "passive"))
    )
    (net (code "88") (name "unconnected-(JP1-Pad33)") (class "Default")
      (node (ref "JP1") (pin "33") (pinfunction "33_33") (pintype "passive"))
    )
    (net (code "89") (name "unconnected-(JP1-Pad35)") (class "Default")
      (node (ref "JP1") (pin "35") (pinfunction "35_35") (pintype "passive"))
    )
    (net (code "90") (name "unconnected-(JP1-Pad37)") (class "Default")
      (node (ref "JP1") (pin "37") (pinfunction "37_37") (pintype "passive"))
    )
    (net (code "91") (name "unconnected-(JP1-Pad38)") (class "Default")
      (node (ref "JP1") (pin "38") (pinfunction "38_38") (pintype "passive"))
    )
    (net (code "92") (name "unconnected-(JP1-Pad40)") (class "Default")
      (node (ref "JP1") (pin "40") (pinfunction "40_40") (pintype "passive"))
    )
    (net (code "93") (name "unconnected-(U$5-NC-Pad14)") (class "Default")
      (node (ref "U$5") (pin "14") (pinfunction "NC_14") (pintype "bidirectional"))
    )
    (net (code "94") (name "unconnected-(U$5-P0B-Pad13)") (class "Default")
      (node (ref "U$5") (pin "13") (pinfunction "P0B_13") (pintype "bidirectional"))
    )
    (net (code "95") (name "unconnected-(U$5-P1B-Pad8)") (class "Default")
      (node (ref "U$5") (pin "8") (pinfunction "P1B_8") (pintype "bidirectional"))
    )
    (net (code "96") (name "unconnected-(U$5-P2B-Pad18)") (class "Default")
      (node (ref "U$5") (pin "18") (pinfunction "P2B_18") (pintype "bidirectional"))
    )
    (net (code "97") (name "unconnected-(U$5-P3B-Pad3)") (class "Default")
      (node (ref "U$5") (pin "3") (pinfunction "P3B_3") (pintype "bidirectional"))
    )
    (net (code "98") (name "unconnected-(U$9-5V_MIDIIN_NC-Pad15)") (class "Default")
      (node (ref "U$9") (pin "15") (pinfunction "5V_MIDIIN_NC_15") (pintype "bidirectional"))
    )
    (net (code "99") (name "unconnected-(U$9-GND_MIDIOUT-Pad12)") (class "Default")
      (node (ref "U$9") (pin "12") (pinfunction "GND_MIDIOUT_12") (pintype "bidirectional"))
    )
  )
)
